# PowerSupply.net
KiCad netlist of a schematic drawn in Altium Designer
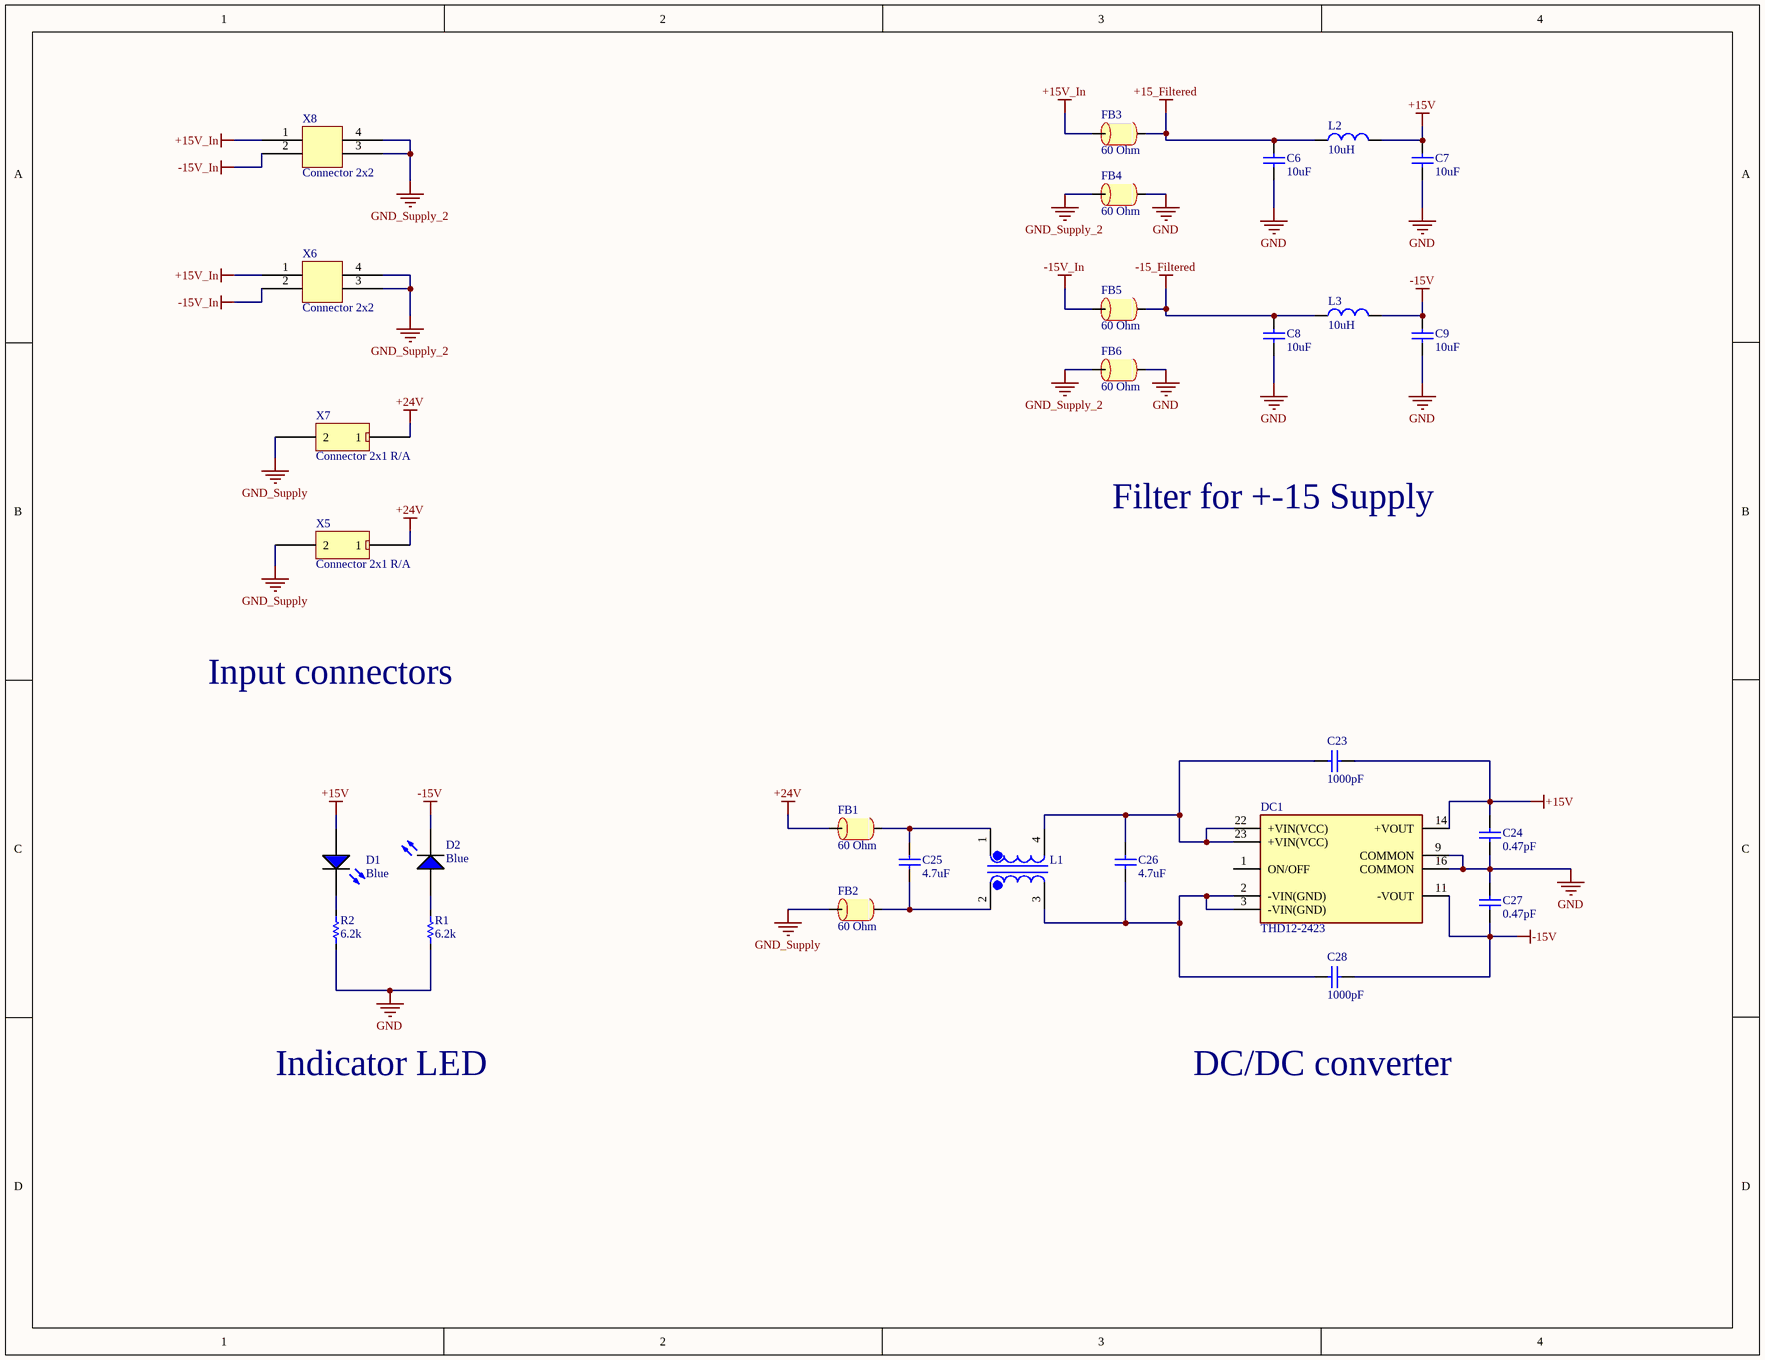
[diagram p0: PowerSupply.SchDoc]

(export (version "E")
  (design (tool "Eeschema 10.0.6"))
  (components
    (comp (ref "C6")
      (value "10uF")
      (footprint "CAP_1210")
      (description "10µF ±10% 50V Ceramic Capacitor X7R 1210 (3225 Metric)")
      (fields (field (name "MF") "KEMET") (field (name "CREATED") "2020_06_15_DAarancibia"))
      (libsource (lib "Voltage_Transducers_Lib") (part "Cap_1210"))
    )
    (comp (ref "C7")
      (value "10uF")
      (footprint "CAP_1210")
      (description "10µF ±10% 50V Ceramic Capacitor X7R 1210 (3225 Metric)")
      (fields (field (name "MF") "KEMET") (field (name "CREATED") "2020_06_15_DAarancibia"))
      (libsource (lib "Voltage_Transducers_Lib") (part "Cap_1210"))
    )
    (comp (ref "C8")
      (value "10uF")
      (footprint "CAP_1210")
      (description "10µF ±10% 50V Ceramic Capacitor X7R 1210 (3225 Metric)")
      (fields (field (name "MF") "KEMET") (field (name "CREATED") "2020_06_15_DAarancibia"))
      (libsource (lib "Voltage_Transducers_Lib") (part "Cap_1210"))
    )
    (comp (ref "C9")
      (value "10uF")
      (footprint "CAP_1210")
      (description "10µF ±10% 50V Ceramic Capacitor X7R 1210 (3225 Metric)")
      (fields (field (name "MF") "KEMET") (field (name "CREATED") "2020_06_15_DAarancibia"))
      (libsource (lib "Voltage_Transducers_Lib") (part "Cap_1210"))
    )
    (comp (ref "C23")
      (value "1000pF")
      (footprint "CAP_1206")
      (description "Cap Ceramic 0.001uF 2000V X7R 10% SMD 1206 125°C Embossed Plastic T/R")
      (fields
        (field (name "MANUFACTURER") "KEMET")
        (field (name "MANUFACTURER PART NUMBER") "C1206C102KGRACAUTO")
      )
      (libsource (lib "Current_SCH_Libraries") (part "C1206C102KGRACAUTO"))
    )
    (comp (ref "C24")
      (value "0.47pF")
      (footprint "CAP_0603")
      (description "Surface Mount Ceramic Multilayer Capacitor 0.47pF 0.25pF C0G 50V 0603 Paper T/R")
      (fields
        (field (name "MANUFACTURER") "Yageo")
        (field (name "MANUFACTURER PART NUMBER") "CC0603CRNPO9BNR47")
      )
      (libsource (lib "Current_SCH_Libraries") (part "CC0603CRNPO9BNR47"))
    )
    (comp (ref "C25")
      (value "4.7uF")
      (footprint "CAP_1206")
      (description "Cap Ceramic 4.7uF 50V X5R 20% Pad SMD 1206 85C Low ESR Automotive T/R")
      (fields
        (field (name "MANUFACTURER") "Taiyo Yuden")
        (field (name "MANUFACTURER PART NUMBER") "UMK316ABJ475MLHT")
      )
      (libsource (lib "Current_SCH_Libraries") (part "UMK316ABJ475MLHT"))
    )
    (comp (ref "C26")
      (value "4.7uF")
      (footprint "CAP_1206")
      (description "Cap Ceramic 4.7uF 50V X5R 20% Pad SMD 1206 85C Low ESR Automotive T/R")
      (fields
        (field (name "MANUFACTURER") "Taiyo Yuden")
        (field (name "MANUFACTURER PART NUMBER") "UMK316ABJ475MLHT")
      )
      (libsource (lib "Current_SCH_Libraries") (part "UMK316ABJ475MLHT"))
    )
    (comp (ref "C27")
      (value "0.47pF")
      (footprint "CAP_0603")
      (description "Surface Mount Ceramic Multilayer Capacitor 0.47pF 0.25pF C0G 50V 0603 Paper T/R")
      (fields
        (field (name "MANUFACTURER") "Yageo")
        (field (name "MANUFACTURER PART NUMBER") "CC0603CRNPO9BNR47")
      )
      (libsource (lib "Current_SCH_Libraries") (part "CC0603CRNPO9BNR47"))
    )
    (comp (ref "C28")
      (value "1000pF")
      (footprint "CAP_1206")
      (description "Cap Ceramic 0.001uF 2000V X7R 10% SMD 1206 125°C Embossed Plastic T/R")
      (fields
        (field (name "MANUFACTURER") "KEMET")
        (field (name "MANUFACTURER PART NUMBER") "C1206C102KGRACAUTO")
      )
      (libsource (lib "Current_SCH_Libraries") (part "C1206C102KGRACAUTO"))
    )
    (comp (ref "D1")
      (value "Blue")
      (footprint "LED_0603_Blue")
      (description "Blue 470nm LED Indication - Discrete 3.2V 0603 (1608 Metric)")
      (fields (field (name "MF") "Würth Elektronik") (field (name "CREATED") "2020_07_06_DAarancibia"))
      (libsource (lib "Current_SCH_Libraries") (part "Led_0603_Blue"))
    )
    (comp (ref "D2")
      (value "Blue")
      (footprint "LED_0603_Blue")
      (description "Blue 470nm LED Indication - Discrete 3.2V 0603 (1608 Metric)")
      (fields (field (name "MF") "Würth Elektronik") (field (name "CREATED") "2020_07_06_DAarancibia"))
      (libsource (lib "Current_SCH_Libraries") (part "Led_0603_Blue"))
    )
    (comp (ref "DC1")
      (value "THD12-2423")
      (footprint "THD 12-2423")
      (description "TRACOPOWER Isolated DC-DC Converter, Vin 18  36 V dc, Vout 15V dc, I/O isolation 1500V dc")
      (fields (field (name "MANUFACTURER") "Traco Power"))
      (libsource (lib "Current_SCH_Libraries") (part "THD12-2423"))
    )
    (comp (ref "FB1")
      (value "60 Ohm")
      (footprint "FB_1206")
      (description "60 Ohms @ 100MHz 1 Power Line Ferrite Bead 1206 (3216 Metric) 4A 10mOhm")
      (fields (field (name "MF") "Taiyo Yuden") (field (name "CREATED") "2020_07_06_DAarancibia"))
      (libsource (lib "Current_SCH_Libraries") (part "Ferrite Bead"))
    )
    (comp (ref "FB2")
      (value "60 Ohm")
      (footprint "FB_1206")
      (description "60 Ohms @ 100MHz 1 Power Line Ferrite Bead 1206 (3216 Metric) 4A 10mOhm")
      (fields (field (name "MF") "Taiyo Yuden") (field (name "CREATED") "2020_07_06_DAarancibia"))
      (libsource (lib "Current_SCH_Libraries") (part "Ferrite Bead"))
    )
    (comp (ref "FB3")
      (value "60 Ohm")
      (footprint "FB_1206")
      (description "60 Ohms @ 100MHz 1 Power Line Ferrite Bead 1206 (3216 Metric) 4A 10mOhm")
      (fields (field (name "MF") "Taiyo Yuden") (field (name "CREATED") "2020_07_06_DAarancibia"))
      (libsource (lib "Voltage_Transducers_Lib") (part "Ferrite Bead"))
    )
    (comp (ref "FB4")
      (value "60 Ohm")
      (footprint "FB_1206")
      (description "60 Ohms @ 100MHz 1 Power Line Ferrite Bead 1206 (3216 Metric) 4A 10mOhm")
      (fields (field (name "MF") "Taiyo Yuden") (field (name "CREATED") "2020_07_06_DAarancibia"))
      (libsource (lib "Voltage_Transducers_Lib") (part "Ferrite Bead"))
    )
    (comp (ref "FB5")
      (value "60 Ohm")
      (footprint "FB_1206")
      (description "60 Ohms @ 100MHz 1 Power Line Ferrite Bead 1206 (3216 Metric) 4A 10mOhm")
      (fields (field (name "MF") "Taiyo Yuden") (field (name "CREATED") "2020_07_06_DAarancibia"))
      (libsource (lib "Voltage_Transducers_Lib") (part "Ferrite Bead"))
    )
    (comp (ref "FB6")
      (value "60 Ohm")
      (footprint "FB_1206")
      (description "60 Ohms @ 100MHz 1 Power Line Ferrite Bead 1206 (3216 Metric) 4A 10mOhm")
      (fields (field (name "MF") "Taiyo Yuden") (field (name "CREATED") "2020_07_06_DAarancibia"))
      (libsource (lib "Voltage_Transducers_Lib") (part "Ferrite Bead"))
    )
    (comp (ref "L1")
      (value "SC-07-04GJ")
      (footprint "SC-07-04GJ")
      (description "Ind Common Mode Choke 0.36mH 7A 14m Ohm Toroid 4-Pin Radial Tray")
      (fields (field (name "MANUFACTURER") "KEMET"))
      (libsource (lib "Current_SCH_Libraries") (part "SC-07-04GJ"))
    )
    (comp (ref "L2")
      (value "10uH")
      (footprint "INDUCTOR_1210")
      (description "10µH Unshielded Wirewound Inductor 700mA 350mOhm Max 1210 (3225 Metric)")
      (fields (field (name "MF") "Taiyo Yuden") (field (name "CREATED") "2020_07_06_DAarancibia"))
      (libsource (lib "Voltage_Transducers_Lib") (part "Inductor_1210"))
    )
    (comp (ref "L3")
      (value "10uH")
      (footprint "INDUCTOR_1210")
      (description "10µH Unshielded Wirewound Inductor 700mA 350mOhm Max 1210 (3225 Metric)")
      (fields (field (name "MF") "Taiyo Yuden") (field (name "CREATED") "2020_07_06_DAarancibia"))
      (libsource (lib "Voltage_Transducers_Lib") (part "Inductor_1210"))
    )
    (comp (ref "R1")
      (value "6.2k")
      (footprint "RES_0603")
      (fields
        (field (name "MF") "Panasonic Electronic Components")
        (field (name "CREATED") "2020_06_15_DAarancibia")
      )
      (libsource (lib "Current_SCH_Libraries") (part "Res_0603"))
    )
    (comp (ref "R2")
      (value "6.2k")
      (footprint "RES_0603")
      (fields
        (field (name "MF") "Panasonic Electronic Components")
        (field (name "CREATED") "2020_06_15_DAarancibia")
      )
      (libsource (lib "Current_SCH_Libraries") (part "Res_0603"))
    )
    (comp (ref "X5")
      (value "Connector 2x1 R/A")
      (footprint "CON_WR-MPC4-649002227222")
      (description "Connector Header Through Hole, Right Angle 2 position 0.165\" (4.20mm)")
      (fields
        (field (name "MF") "Würth Elektronik")
        (field (name "MPN") "649002227222")
        (field (name "CREATED") "2020_06_14_DArancibia")
      )
      (libsource (lib "Current_SCH_Libraries") (part "Con_WR-MPC4_2x1"))
    )
    (comp (ref "X6")
      (value "Connector 2x2")
      (footprint "0874270402")
      (description "Conn Power HDR 4 POS 4.2mm Solder RA Thru-Hole 4 Terminal 1 Port Mini-Fit Jr™ Frame")
      (fields (field (name "MANUFACTURER") "Molex") (field (name "MANUFACTURER PART NUMBER") "0874270402"))
      (libsource (lib "Current_SCH_Libraries") (part "0874270402"))
    )
    (comp (ref "X7")
      (value "Connector 2x1 R/A")
      (footprint "CON_WR-MPC4-649002227222")
      (description "Connector Header Through Hole, Right Angle 2 position 0.165\" (4.20mm)")
      (fields
        (field (name "MF") "Würth Elektronik")
        (field (name "MPN") "649002227222")
        (field (name "CREATED") "2020_06_14_DArancibia")
      )
      (libsource (lib "Current_SCH_Libraries") (part "Con_WR-MPC4_2x1"))
    )
    (comp (ref "X8")
      (value "Connector 2x2")
      (footprint "0874270402")
      (description "Conn Power HDR 4 POS 4.2mm Solder RA Thru-Hole 4 Terminal 1 Port Mini-Fit Jr™ Frame")
      (fields (field (name "MANUFACTURER") "Molex") (field (name "MANUFACTURER PART NUMBER") "0874270402"))
      (libsource (lib "Current_SCH_Libraries") (part "0874270402"))
    )
  )
  (nets
    (net (code "1") (name "+15V") (class "Default")
      (node (ref "C23") (pin "2") (pinfunction "2_2") (pintype "passive"))
      (node (ref "C24") (pin "1") (pinfunction "1_1") (pintype "passive"))
      (node (ref "C7") (pin "1") (pinfunction "1_1") (pintype "passive"))
      (node (ref "D1") (pin "1") (pinfunction "A_1") (pintype "passive"))
      (node (ref "DC1") (pin "14") (pinfunction "+VOUT_14") (pintype "passive"))
      (node (ref "L2") (pin "2") (pinfunction "2_2") (pintype "passive"))
    )
    (net (code "2") (name "+15V_In") (class "Default")
      (node (ref "FB3") (pin "1") (pintype "passive"))
      (node (ref "X6") (pin "1") (pintype "passive"))
      (node (ref "X8") (pin "1") (pintype "passive"))
    )
    (net (code "3") (name "+15_Filtered") (class "Default")
      (node (ref "C6") (pin "1") (pinfunction "1_1") (pintype "passive"))
      (node (ref "FB3") (pin "2") (pintype "passive"))
      (node (ref "L2") (pin "1") (pinfunction "1_1") (pintype "passive"))
    )
    (net (code "4") (name "+24V") (class "Default")
      (node (ref "FB1") (pin "1") (pintype "passive"))
      (node (ref "X5") (pin "1") (pinfunction "1_1") (pintype "passive"))
      (node (ref "X7") (pin "1") (pinfunction "1_1") (pintype "passive"))
    )
    (net (code "5") (name "-15V") (class "Default")
      (node (ref "C27") (pin "2") (pinfunction "2_2") (pintype "passive"))
      (node (ref "C28") (pin "2") (pinfunction "2_2") (pintype "passive"))
      (node (ref "C9") (pin "1") (pinfunction "1_1") (pintype "passive"))
      (node (ref "D2") (pin "2") (pinfunction "K_2") (pintype "passive"))
      (node (ref "DC1") (pin "11") (pinfunction "-VOUT_11") (pintype "passive"))
      (node (ref "L3") (pin "2") (pinfunction "2_2") (pintype "passive"))
    )
    (net (code "6") (name "-15V_In") (class "Default")
      (node (ref "FB5") (pin "1") (pintype "passive"))
      (node (ref "X6") (pin "2") (pintype "passive"))
      (node (ref "X8") (pin "2") (pintype "passive"))
    )
    (net (code "7") (name "-15_Filtered") (class "Default")
      (node (ref "C8") (pin "1") (pinfunction "1_1") (pintype "passive"))
      (node (ref "FB5") (pin "2") (pintype "passive"))
      (node (ref "L3") (pin "1") (pinfunction "1_1") (pintype "passive"))
    )
    (net (code "8") (name "GND") (class "Default")
      (node (ref "C24") (pin "2") (pinfunction "2_2") (pintype "passive"))
      (node (ref "C27") (pin "1") (pinfunction "1_1") (pintype "passive"))
      (node (ref "C6") (pin "2") (pinfunction "2_2") (pintype "passive"))
      (node (ref "C7") (pin "2") (pinfunction "2_2") (pintype "passive"))
      (node (ref "C8") (pin "2") (pinfunction "2_2") (pintype "passive"))
      (node (ref "C9") (pin "2") (pinfunction "2_2") (pintype "passive"))
      (node (ref "DC1") (pin "16") (pinfunction "COMMON_16") (pintype "passive"))
      (node (ref "DC1") (pin "9") (pinfunction "COMMON_9") (pintype "passive"))
      (node (ref "FB4") (pin "2") (pintype "passive"))
      (node (ref "FB6") (pin "2") (pintype "passive"))
      (node (ref "R1") (pin "1") (pinfunction "1_1") (pintype "passive"))
      (node (ref "R2") (pin "1") (pinfunction "1_1") (pintype "passive"))
    )
    (net (code "9") (name "GND_Supply") (class "Default")
      (node (ref "FB2") (pin "1") (pintype "passive"))
      (node (ref "X5") (pin "2") (pinfunction "2_2") (pintype "passive"))
      (node (ref "X7") (pin "2") (pinfunction "2_2") (pintype "passive"))
    )
    (net (code "10") (name "GND_Supply_2") (class "Default")
      (node (ref "FB4") (pin "1") (pintype "passive"))
      (node (ref "FB6") (pin "1") (pintype "passive"))
      (node (ref "X6") (pin "3") (pintype "passive"))
      (node (ref "X6") (pin "4") (pintype "passive"))
      (node (ref "X8") (pin "3") (pintype "passive"))
      (node (ref "X8") (pin "4") (pintype "passive"))
    )
    (net (code "11") (name "Net-(C23-Pad1)") (class "Default")
      (node (ref "C23") (pin "1") (pinfunction "1_1") (pintype "passive"))
      (node (ref "C26") (pin "1") (pinfunction "1_1") (pintype "passive"))
      (node (ref "DC1") (pin "22") (pinfunction "+VIN(VCC)_22") (pintype "passive"))
      (node (ref "DC1") (pin "23") (pinfunction "+VIN(VCC)_23") (pintype "passive"))
      (node (ref "L1") (pin "4") (pinfunction "4_4") (pintype "passive"))
    )
    (net (code "12") (name "Net-(C25-Pad1)") (class "Default")
      (node (ref "C25") (pin "1") (pinfunction "1_1") (pintype "passive"))
      (node (ref "FB1") (pin "2") (pintype "passive"))
      (node (ref "L1") (pin "1") (pinfunction "1_1") (pintype "passive"))
    )
    (net (code "13") (name "Net-(C25-Pad2)") (class "Default")
      (node (ref "C25") (pin "2") (pinfunction "2_2") (pintype "passive"))
      (node (ref "FB2") (pin "2") (pintype "passive"))
      (node (ref "L1") (pin "2") (pinfunction "2_2") (pintype "passive"))
    )
    (net (code "14") (name "Net-(C26-Pad2)") (class "Default")
      (node (ref "C26") (pin "2") (pinfunction "2_2") (pintype "passive"))
      (node (ref "C28") (pin "1") (pinfunction "1_1") (pintype "passive"))
      (node (ref "DC1") (pin "2") (pinfunction "-VIN(GND)_2") (pintype "passive"))
      (node (ref "DC1") (pin "3") (pinfunction "-VIN(GND)_3") (pintype "passive"))
      (node (ref "L1") (pin "3") (pinfunction "3_3") (pintype "passive"))
    )
    (net (code "15") (name "Net-(D1-K)") (class "Default")
      (node (ref "D1") (pin "2") (pinfunction "K_2") (pintype "passive"))
      (node (ref "R2") (pin "2") (pinfunction "2_2") (pintype "passive"))
    )
    (net (code "16") (name "Net-(D2-A)") (class "Default")
      (node (ref "D2") (pin "1") (pinfunction "A_1") (pintype "passive"))
      (node (ref "R1") (pin "2") (pinfunction "2_2") (pintype "passive"))
    )
    (net (code "17") (name "unconnected-(DC1-ON{slash}OFF-Pad1)") (class "Default")
      (node (ref "DC1") (pin "1") (pinfunction "ON/OFF_1") (pintype "passive"))
    )
  )
)
